# Connectors.net
KiCad netlist of a schematic drawn in Altium Designer
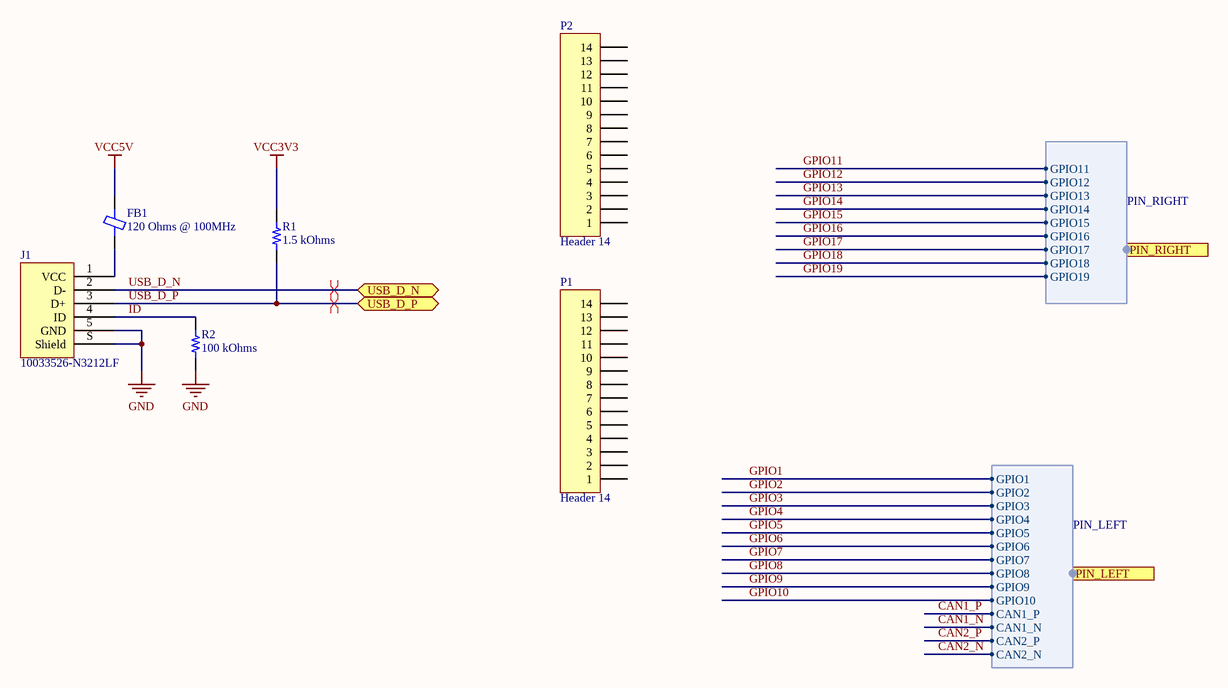
[diagram p0: Connectors.SchDoc]

(export (version "E")
  (design (tool "Eeschema 10.0.6"))
  (components
    (comp (ref "FB1")
      (value "120 Ohms @ 100MHz")
      (footprint "FER 0805_2012")
      (description "FERRITE BEAD 120 OHM 0805 1LN")
      (fields (field (name "PART NUMBER") "742792023") (field (name "MANUFACTURER") "Würth Elektronik"))
      (libsource (lib "Celestial") (part "Ferrite Chip"))
    )
    (comp (ref "J1")
      (value "10033526-N3212LF")
      (footprint "FCI USB 10033526-N3212LF")
      (description "CONN RCPT MINI USB B 5POS SMD RA")
      (fields (field (name "MANUFACTURER") "Amphenol ICC (FCI)"))
      (libsource (lib "Celestial") (part "USB 2.0 Type B Micro"))
    )
    (comp (ref "P1")
      (value "Header 14")
      (footprint "HDR1X14")
      (description "Header, 14-Pin")
      (fields (field (name "PUBLISHER") "Altium Limited"))
      (libsource (lib "Miscellaneous Connectors") (part "Header 14"))
    )
    (comp (ref "P2")
      (value "Header 14")
      (footprint "HDR1X14")
      (description "Header, 14-Pin")
      (fields (field (name "PUBLISHER") "Altium Limited"))
      (libsource (lib "Miscellaneous Connectors") (part "Header 14"))
    )
    (comp (ref "R1")
      (value "1.5 kOhms")
      (footprint "RES 0402_1005")
      (description "RES SMD 1.5K OHM 0.5% 1/16W 0402")
      (fields (field (name "PART NUMBER") "RR0510P-152-D") (field (name "MANUFACTURER") "Susumu"))
      (libsource (lib "Celestial") (part "Resistor"))
    )
    (comp (ref "R2")
      (value "100 kOhms")
      (footprint "RES 0402_1005")
      (description "RES 100K OHM 0.1% 1/10W 0402")
      (fields
        (field (name "PART NUMBER") "RP73PF1E100KBTD")
        (field (name "MANUFACTURER") "TE Connectivity Passive Product")
      )
      (libsource (lib "Celestial") (part "Resistor"))
    )
  )
  (nets
    (net (code "26") (name "/ID") (class "Default")
      (node (ref "J1") (pin "4") (pinfunction "ID_4") (pintype "passive"))
      (node (ref "R2") (pin "2") (pinfunction "2_2") (pintype "passive"))
    )
    (net (code "27") (name "/USB_D_N") (class "Default")
      (node (ref "J1") (pin "2") (pinfunction "D-_2") (pintype "passive"))
    )
    (net (code "28") (name "/USB_D_P") (class "Default")
      (node (ref "J1") (pin "3") (pinfunction "D+_3") (pintype "passive"))
      (node (ref "R1") (pin "1") (pinfunction "1_1") (pintype "passive"))
    )
    (net (code "31") (name "GND") (class "Default")
      (node (ref "J1") (pin "5") (pinfunction "GND_5") (pintype "passive"))
      (node (ref "J1") (pin "S") (pinfunction "Shield_S") (pintype "passive"))
      (node (ref "R2") (pin "1") (pinfunction "1_1") (pintype "passive"))
    )
    (net (code "32") (name "Net-(J1-VCC)") (class "Default")
      (node (ref "FB1") (pin "1") (pinfunction "1_1") (pintype "passive"))
      (node (ref "J1") (pin "1") (pinfunction "VCC_1") (pintype "passive"))
    )
    (net (code "33") (name "VCC3V3") (class "Default")
      (node (ref "R1") (pin "2") (pinfunction "2_2") (pintype "passive"))
    )
    (net (code "34") (name "VCC5V") (class "Default")
      (node (ref "FB1") (pin "2") (pinfunction "2_2") (pintype "passive"))
    )
    (net (code "35") (name "unconnected-(P1-Pad1)") (class "Default")
      (node (ref "P1") (pin "1") (pinfunction "1_1") (pintype "passive"))
    )
    (net (code "36") (name "unconnected-(P1-Pad2)") (class "Default")
      (node (ref "P1") (pin "2") (pinfunction "2_2") (pintype "passive"))
    )
    (net (code "37") (name "unconnected-(P1-Pad3)") (class "Default")
      (node (ref "P1") (pin "3") (pinfunction "3_3") (pintype "passive"))
    )
    (net (code "38") (name "unconnected-(P1-Pad4)") (class "Default")
      (node (ref "P1") (pin "4") (pinfunction "4_4") (pintype "passive"))
    )
    (net (code "39") (name "unconnected-(P1-Pad5)") (class "Default")
      (node (ref "P1") (pin "5") (pinfunction "5_5") (pintype "passive"))
    )
    (net (code "40") (name "unconnected-(P1-Pad6)") (class "Default")
      (node (ref "P1") (pin "6") (pinfunction "6_6") (pintype "passive"))
    )
    (net (code "41") (name "unconnected-(P1-Pad7)") (class "Default")
      (node (ref "P1") (pin "7") (pinfunction "7_7") (pintype "passive"))
    )
    (net (code "42") (name "unconnected-(P1-Pad8)") (class "Default")
      (node (ref "P1") (pin "8") (pinfunction "8_8") (pintype "passive"))
    )
    (net (code "43") (name "unconnected-(P1-Pad9)") (class "Default")
      (node (ref "P1") (pin "9") (pinfunction "9_9") (pintype "passive"))
    )
    (net (code "44") (name "unconnected-(P1-Pad10)") (class "Default")
      (node (ref "P1") (pin "10") (pinfunction "10_10") (pintype "passive"))
    )
    (net (code "45") (name "unconnected-(P1-Pad11)") (class "Default")
      (node (ref "P1") (pin "11") (pinfunction "11_11") (pintype "passive"))
    )
    (net (code "46") (name "unconnected-(P1-Pad12)") (class "Default")
      (node (ref "P1") (pin "12") (pinfunction "12_12") (pintype "passive"))
    )
    (net (code "47") (name "unconnected-(P1-Pad13)") (class "Default")
      (node (ref "P1") (pin "13") (pinfunction "13_13") (pintype "passive"))
    )
    (net (code "48") (name "unconnected-(P1-Pad14)") (class "Default")
      (node (ref "P1") (pin "14") (pinfunction "14_14") (pintype "passive"))
    )
    (net (code "49") (name "unconnected-(P2-Pad1)") (class "Default")
      (node (ref "P2") (pin "1") (pinfunction "1_1") (pintype "passive"))
    )
    (net (code "50") (name "unconnected-(P2-Pad2)") (class "Default")
      (node (ref "P2") (pin "2") (pinfunction "2_2") (pintype "passive"))
    )
    (net (code "51") (name "unconnected-(P2-Pad3)") (class "Default")
      (node (ref "P2") (pin "3") (pinfunction "3_3") (pintype "passive"))
    )
    (net (code "52") (name "unconnected-(P2-Pad4)") (class "Default")
      (node (ref "P2") (pin "4") (pinfunction "4_4") (pintype "passive"))
    )
    (net (code "53") (name "unconnected-(P2-Pad5)") (class "Default")
      (node (ref "P2") (pin "5") (pinfunction "5_5") (pintype "passive"))
    )
    (net (code "54") (name "unconnected-(P2-Pad6)") (class "Default")
      (node (ref "P2") (pin "6") (pinfunction "6_6") (pintype "passive"))
    )
    (net (code "55") (name "unconnected-(P2-Pad7)") (class "Default")
      (node (ref "P2") (pin "7") (pinfunction "7_7") (pintype "passive"))
    )
    (net (code "56") (name "unconnected-(P2-Pad8)") (class "Default")
      (node (ref "P2") (pin "8") (pinfunction "8_8") (pintype "passive"))
    )
    (net (code "57") (name "unconnected-(P2-Pad9)") (class "Default")
      (node (ref "P2") (pin "9") (pinfunction "9_9") (pintype "passive"))
    )
    (net (code "58") (name "unconnected-(P2-Pad10)") (class "Default")
      (node (ref "P2") (pin "10") (pinfunction "10_10") (pintype "passive"))
    )
    (net (code "59") (name "unconnected-(P2-Pad11)") (class "Default")
      (node (ref "P2") (pin "11") (pinfunction "11_11") (pintype "passive"))
    )
    (net (code "60") (name "unconnected-(P2-Pad12)") (class "Default")
      (node (ref "P2") (pin "12") (pinfunction "12_12") (pintype "passive"))
    )
    (net (code "61") (name "unconnected-(P2-Pad13)") (class "Default")
      (node (ref "P2") (pin "13") (pinfunction "13_13") (pintype "passive"))
    )
    (net (code "62") (name "unconnected-(P2-Pad14)") (class "Default")
      (node (ref "P2") (pin "14") (pinfunction "14_14") (pintype "passive"))
    )
  )
)
